# quad_cape.net
KiCad netlist of a schematic drawn in EAGLE
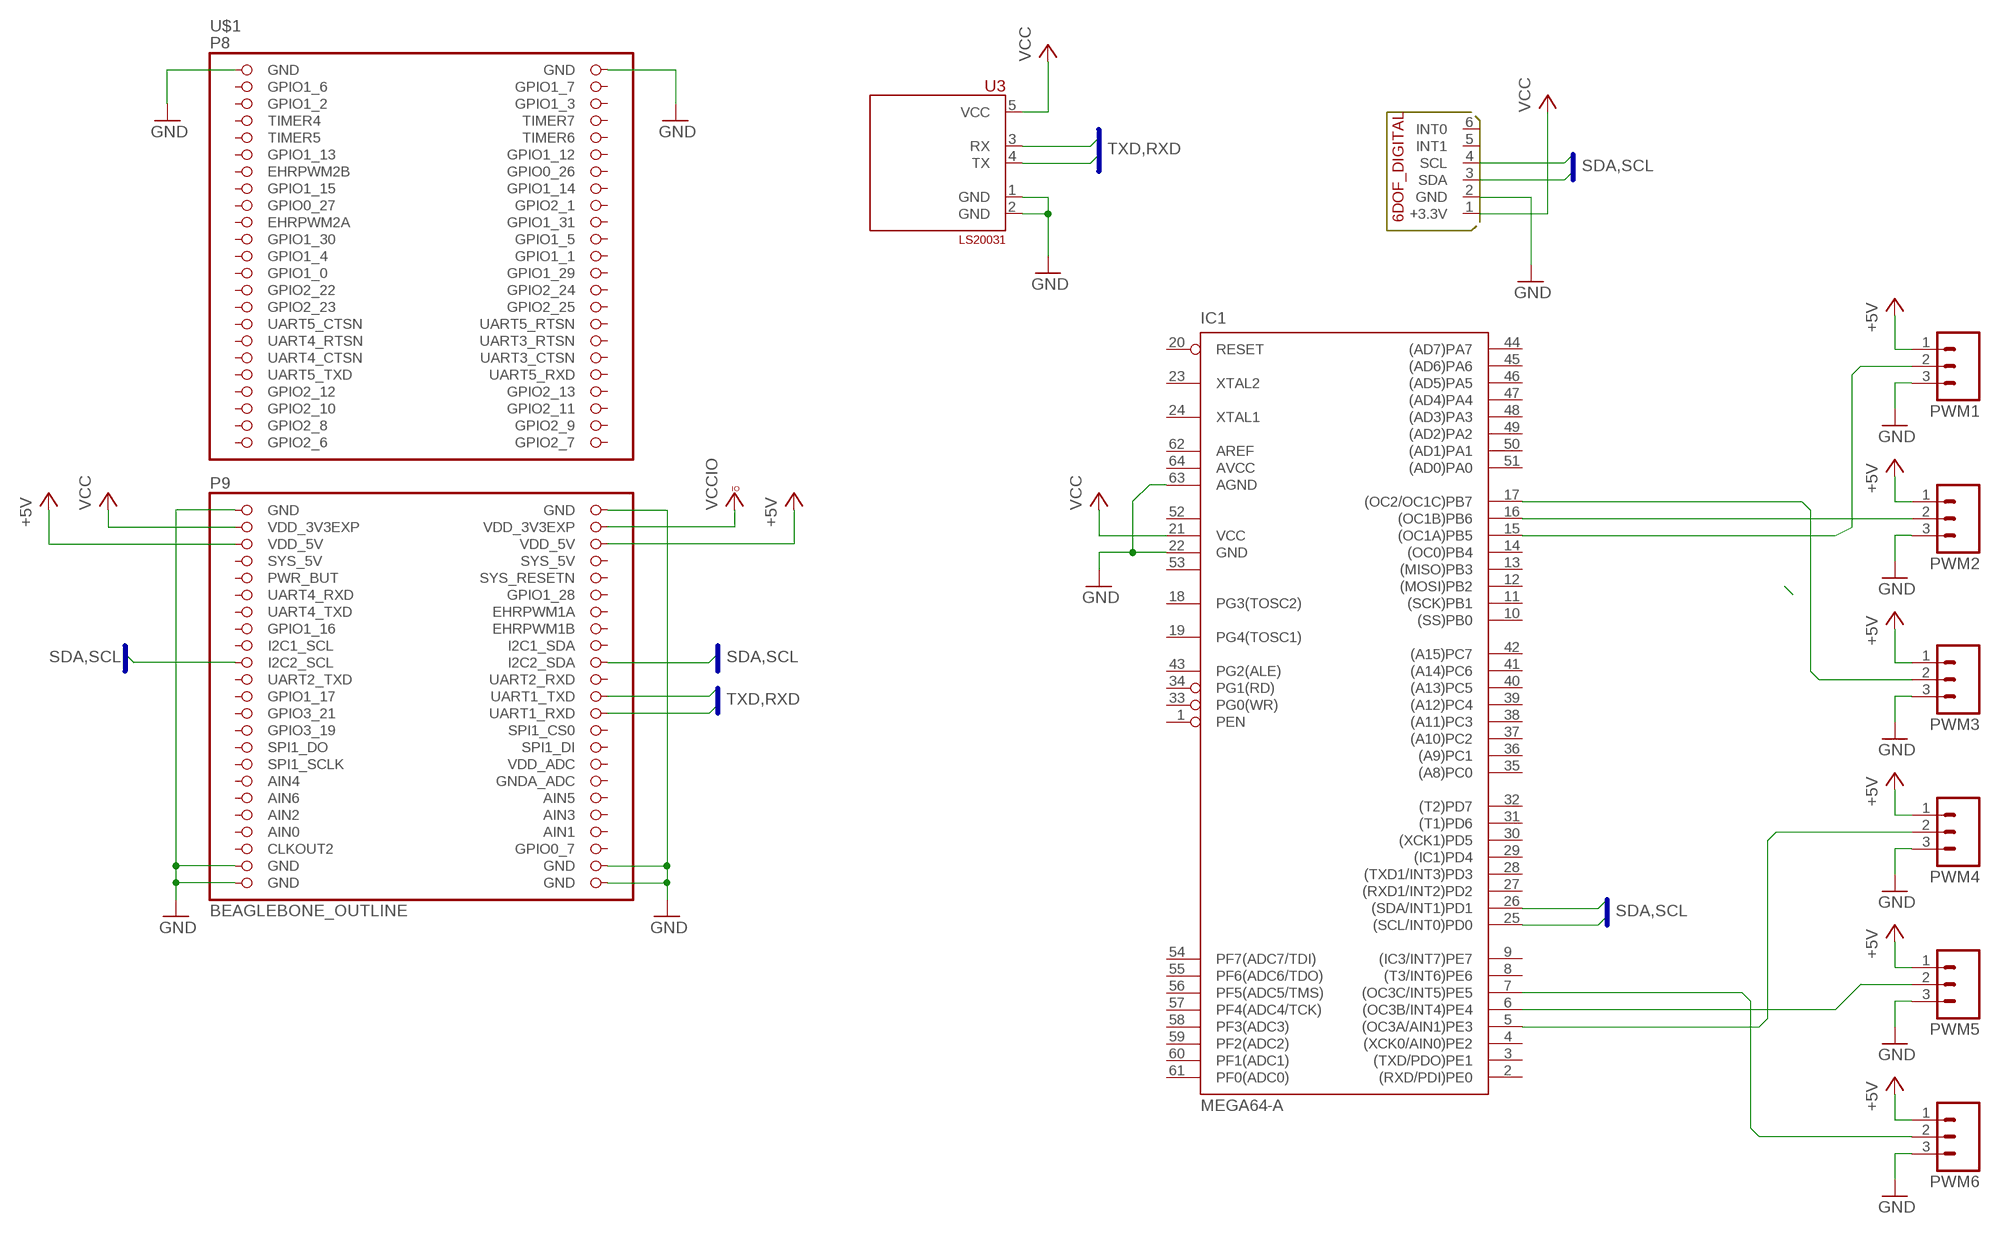
[diagram p0: schematic, sheet 1]

(export (version "E")
  (design (tool "Eeschema 10.0.6"))
  (components
    (comp (ref "IC1")
      (value "MEGA64-A")
      (footprint "eagle-import:TQFP64")
      (libsource (lib "eagle-import") (part "MEGA64-A"))
    )
    (comp (ref "PWM1")
      (value "M03")
      (footprint "eagle-import:JST-3-SMD")
      (libsource (lib "eagle-import") (part "M03"))
    )
    (comp (ref "PWM2")
      (value "M03")
      (footprint "eagle-import:JST-3-SMD")
      (libsource (lib "eagle-import") (part "M03"))
    )
    (comp (ref "PWM3")
      (value "M03")
      (footprint "eagle-import:JST-3-SMD")
      (libsource (lib "eagle-import") (part "M03"))
    )
    (comp (ref "PWM4")
      (value "M03")
      (footprint "eagle-import:JST-3-SMD")
      (libsource (lib "eagle-import") (part "M03"))
    )
    (comp (ref "PWM5")
      (value "M03")
      (footprint "eagle-import:JST-3-SMD")
      (libsource (lib "eagle-import") (part "M03"))
    )
    (comp (ref "PWM6")
      (value "M03")
      (footprint "eagle-import:JST-3-SMD")
      (libsource (lib "eagle-import") (part "M03"))
    )
    (comp (ref "U$1")
      (value "BEAGLEBONE_OUTLINE")
      (footprint "eagle-import:BEAGLEBONE_SHIELD")
      (libsource (lib "eagle-import") (part "BEAGLEBONE_OUTLINE"))
    )
    (comp (ref "U$2")
      (value "6DOF-DIGITAL")
      (footprint "eagle-import:6DOF_DIGITAL_V10")
      (libsource (lib "eagle-import") (part "6DOF-DIGITAL"))
    )
    (comp (ref "U3")
      (value "LS20031")
      (footprint "eagle-import:LS20031")
      (libsource (lib "eagle-import") (part "LS20031"))
    )
  )
  (nets
    (net (code "1") (name "+5V") (class "Default")
      (node (ref "PWM1") (pin "1") (pinfunction "1_1") (pintype "passive"))
      (node (ref "PWM2") (pin "1") (pinfunction "1_1") (pintype "passive"))
      (node (ref "PWM3") (pin "1") (pinfunction "1_1") (pintype "passive"))
      (node (ref "PWM4") (pin "1") (pinfunction "1_1") (pintype "passive"))
      (node (ref "PWM5") (pin "1") (pinfunction "1_1") (pintype "passive"))
      (node (ref "PWM6") (pin "1") (pinfunction "1_1") (pintype "passive"))
      (node (ref "U$1") (pin "51") (pinfunction "VDD_5V_51") (pintype "power_in"))
      (node (ref "U$1") (pin "52") (pinfunction "VDD_5V_52") (pintype "power_in"))
    )
    (net (code "2") (name "/AIN0") (class "Default")
      (node (ref "U$1") (pin "85") (pinfunction "AIN0_85") (pintype "power_in"))
    )
    (net (code "3") (name "/AIN3") (class "Default")
      (node (ref "U$1") (pin "84") (pinfunction "AIN3_84") (pintype "power_in"))
    )
    (net (code "4") (name "/GND1") (class "Default")
      (node (ref "IC1") (pin "53") (pinfunction "GND1_53") (pintype "power_in"))
    )
    (net (code "5") (name "/GPIO1_6") (class "Default")
      (node (ref "U$1") (pin "3") (pinfunction "GPIO1_6_3") (pintype "power_in"))
    )
    (net (code "6") (name "/GPIO1_7") (class "Default")
      (node (ref "U$1") (pin "4") (pinfunction "GPIO1_7_4") (pintype "power_in"))
    )
    (net (code "7") (name "/GPIO2_6") (class "Default")
      (node (ref "U$1") (pin "45") (pinfunction "GPIO2_6_45") (pintype "power_in"))
    )
    (net (code "8") (name "/GPIO2_7") (class "Default")
      (node (ref "U$1") (pin "46") (pinfunction "GPIO2_7_46") (pintype "power_in"))
    )
    (net (code "9") (name "/GPIO2_8") (class "Default")
      (node (ref "U$1") (pin "43") (pinfunction "GPIO2_8_43") (pintype "power_in"))
    )
    (net (code "10") (name "/GPIO2_9") (class "Default")
      (node (ref "U$1") (pin "44") (pinfunction "GPIO2_9_44") (pintype "power_in"))
    )
    (net (code "11") (name "/GPIO2_11") (class "Default")
      (node (ref "U$1") (pin "42") (pinfunction "GPIO2_11_42") (pintype "power_in"))
    )
    (net (code "12") (name "/RXD") (class "Default")
      (node (ref "U$1") (pin "72") (pinfunction "UART1_RXD_72") (pintype "passive"))
      (node (ref "U3") (pin "4") (pinfunction "TX_4") (pintype "output"))
    )
    (net (code "13") (name "/SCL") (class "Default")
      (node (ref "IC1") (pin "25") (pinfunction "(SCL/INT0)PD0_25") (pintype "bidirectional"))
      (node (ref "U$1") (pin "65") (pinfunction "I2C2_SCL_65") (pintype "passive"))
      (node (ref "U$2") (pin "4") (pinfunction "SCL_4") (pintype "bidirectional"))
    )
    (net (code "14") (name "/SDA") (class "Default")
      (node (ref "IC1") (pin "26") (pinfunction "(SDA/INT1)PD1_26") (pintype "bidirectional"))
      (node (ref "U$1") (pin "66") (pinfunction "I2C2_SDA_66") (pintype "passive"))
      (node (ref "U$2") (pin "3") (pinfunction "SDA_3") (pintype "bidirectional"))
    )
    (net (code "15") (name "/TXD") (class "Default")
      (node (ref "U$1") (pin "70") (pinfunction "UART1_TXD_70") (pintype "passive"))
      (node (ref "U3") (pin "3") (pinfunction "RX_3") (pintype "input"))
    )
    (net (code "16") (name "/VCC1") (class "Default")
      (node (ref "IC1") (pin "52") (pinfunction "VCC1_52") (pintype "power_in"))
    )
    (net (code "19") (name "GND") (class "Default")
      (node (ref "IC1") (pin "22") (pinfunction "GND_22") (pintype "power_in"))
      (node (ref "IC1") (pin "63") (pinfunction "AGND_63") (pintype "bidirectional"))
      (node (ref "PWM1") (pin "3") (pinfunction "3_3") (pintype "passive"))
      (node (ref "PWM2") (pin "3") (pinfunction "3_3") (pintype "passive"))
      (node (ref "PWM3") (pin "3") (pinfunction "3_3") (pintype "passive"))
      (node (ref "PWM4") (pin "3") (pinfunction "3_3") (pintype "passive"))
      (node (ref "PWM5") (pin "3") (pinfunction "3_3") (pintype "passive"))
      (node (ref "PWM6") (pin "3") (pinfunction "3_3") (pintype "passive"))
      (node (ref "U$1") (pin "1") (pinfunction "GND_1") (pintype "power_in"))
      (node (ref "U$1") (pin "2") (pinfunction "GND_2") (pintype "power_in"))
      (node (ref "U$1") (pin "47") (pinfunction "GND_47") (pintype "power_in"))
      (node (ref "U$1") (pin "48") (pinfunction "GND_48") (pintype "power_in"))
      (node (ref "U$1") (pin "89") (pinfunction "GND_89") (pintype "input"))
      (node (ref "U$1") (pin "90") (pinfunction "GND_90") (pintype "input"))
      (node (ref "U$1") (pin "91") (pinfunction "GND_91") (pintype "input"))
      (node (ref "U$1") (pin "92") (pinfunction "GND_92") (pintype "input"))
      (node (ref "U$2") (pin "2") (pinfunction "GND_2") (pintype "bidirectional"))
      (node (ref "U3") (pin "1") (pinfunction "GND_1") (pintype "power_in"))
      (node (ref "U3") (pin "2") (pinfunction "GND_2") (pintype "power_in"))
    )
    (net (code "20") (name "Net-(IC1-(OC1A)PB5)") (class "Default")
      (node (ref "IC1") (pin "15") (pinfunction "(OC1A)PB5_15") (pintype "bidirectional"))
      (node (ref "PWM1") (pin "2") (pinfunction "2_2") (pintype "passive"))
    )
    (net (code "21") (name "Net-(IC1-(OC1B)PB6)") (class "Default")
      (node (ref "IC1") (pin "16") (pinfunction "(OC1B)PB6_16") (pintype "bidirectional"))
      (node (ref "PWM2") (pin "2") (pinfunction "2_2") (pintype "passive"))
    )
    (net (code "22") (name "Net-(IC1-(OC2{slash}OC1C)PB7)") (class "Default")
      (node (ref "IC1") (pin "17") (pinfunction "(OC2/OC1C)PB7_17") (pintype "bidirectional"))
      (node (ref "PWM3") (pin "2") (pinfunction "2_2") (pintype "passive"))
    )
    (net (code "23") (name "Net-(IC1-(OC3A{slash}AIN1)PE3)") (class "Default")
      (node (ref "IC1") (pin "5") (pinfunction "(OC3A/AIN1)PE3_5") (pintype "bidirectional"))
      (node (ref "PWM4") (pin "2") (pinfunction "2_2") (pintype "passive"))
    )
    (net (code "24") (name "Net-(IC1-(OC3B{slash}INT4)PE4)") (class "Default")
      (node (ref "IC1") (pin "6") (pinfunction "(OC3B/INT4)PE4_6") (pintype "bidirectional"))
      (node (ref "PWM5") (pin "2") (pinfunction "2_2") (pintype "passive"))
    )
    (net (code "25") (name "Net-(IC1-(OC3C{slash}INT5)PE5)") (class "Default")
      (node (ref "IC1") (pin "7") (pinfunction "(OC3C/INT5)PE5_7") (pintype "bidirectional"))
      (node (ref "PWM6") (pin "2") (pinfunction "2_2") (pintype "passive"))
    )
    (net (code "26") (name "VCC") (class "Default")
      (node (ref "IC1") (pin "21") (pinfunction "VCC_21") (pintype "power_in"))
      (node (ref "U$1") (pin "49") (pinfunction "VDD_3V3EXP_49") (pintype "power_in"))
      (node (ref "U$2") (pin "1") (pinfunction "+3.3V_1") (pintype "bidirectional"))
      (node (ref "U3") (pin "5") (pinfunction "VCC_5") (pintype "power_in"))
    )
    (net (code "27") (name "VCCIO") (class "Default")
      (node (ref "U$1") (pin "50") (pinfunction "VDD_3V3EXP_50") (pintype "power_in"))
    )
    (net (code "28") (name "unconnected-(IC1-(A8)PC0-Pad35)") (class "Default")
      (node (ref "IC1") (pin "35") (pinfunction "(A8)PC0_35") (pintype "output"))
    )
    (net (code "29") (name "unconnected-(IC1-(A9)PC1-Pad36)") (class "Default")
      (node (ref "IC1") (pin "36") (pinfunction "(A9)PC1_36") (pintype "output"))
    )
    (net (code "30") (name "unconnected-(IC1-(A10)PC2-Pad37)") (class "Default")
      (node (ref "IC1") (pin "37") (pinfunction "(A10)PC2_37") (pintype "output"))
    )
    (net (code "31") (name "unconnected-(IC1-(A11)PC3-Pad38)") (class "Default")
      (node (ref "IC1") (pin "38") (pinfunction "(A11)PC3_38") (pintype "output"))
    )
    (net (code "32") (name "unconnected-(IC1-(A12)PC4-Pad39)") (class "Default")
      (node (ref "IC1") (pin "39") (pinfunction "(A12)PC4_39") (pintype "output"))
    )
    (net (code "33") (name "unconnected-(IC1-(A13)PC5-Pad40)") (class "Default")
      (node (ref "IC1") (pin "40") (pinfunction "(A13)PC5_40") (pintype "output"))
    )
    (net (code "34") (name "unconnected-(IC1-(A14)PC6-Pad41)") (class "Default")
      (node (ref "IC1") (pin "41") (pinfunction "(A14)PC6_41") (pintype "output"))
    )
    (net (code "35") (name "unconnected-(IC1-(A15)PC7-Pad42)") (class "Default")
      (node (ref "IC1") (pin "42") (pinfunction "(A15)PC7_42") (pintype "output"))
    )
    (net (code "36") (name "unconnected-(IC1-(AD0)PA0-Pad51)") (class "Default")
      (node (ref "IC1") (pin "51") (pinfunction "(AD0)PA0_51") (pintype "bidirectional"))
    )
    (net (code "37") (name "unconnected-(IC1-(AD1)PA1-Pad50)") (class "Default")
      (node (ref "IC1") (pin "50") (pinfunction "(AD1)PA1_50") (pintype "bidirectional"))
    )
    (net (code "38") (name "unconnected-(IC1-(AD2)PA2-Pad49)") (class "Default")
      (node (ref "IC1") (pin "49") (pinfunction "(AD2)PA2_49") (pintype "bidirectional"))
    )
    (net (code "39") (name "unconnected-(IC1-(AD3)PA3-Pad48)") (class "Default")
      (node (ref "IC1") (pin "48") (pinfunction "(AD3)PA3_48") (pintype "bidirectional"))
    )
    (net (code "40") (name "unconnected-(IC1-(AD4)PA4-Pad47)") (class "Default")
      (node (ref "IC1") (pin "47") (pinfunction "(AD4)PA4_47") (pintype "bidirectional"))
    )
    (net (code "41") (name "unconnected-(IC1-(AD5)PA5-Pad46)") (class "Default")
      (node (ref "IC1") (pin "46") (pinfunction "(AD5)PA5_46") (pintype "bidirectional"))
    )
    (net (code "42") (name "unconnected-(IC1-(AD6)PA6-Pad45)") (class "Default")
      (node (ref "IC1") (pin "45") (pinfunction "(AD6)PA6_45") (pintype "bidirectional"))
    )
    (net (code "43") (name "unconnected-(IC1-(AD7)PA7-Pad44)") (class "Default")
      (node (ref "IC1") (pin "44") (pinfunction "(AD7)PA7_44") (pintype "bidirectional"))
    )
    (net (code "44") (name "unconnected-(IC1-(IC1)PD4-Pad29)") (class "Default")
      (node (ref "IC1") (pin "29") (pinfunction "(IC1)PD4_29") (pintype "bidirectional"))
    )
    (net (code "45") (name "unconnected-(IC1-(IC3{slash}INT7)PE7-Pad9)") (class "Default")
      (node (ref "IC1") (pin "9") (pinfunction "(IC3/INT7)PE7_9") (pintype "bidirectional"))
    )
    (net (code "46") (name "unconnected-(IC1-(MISO)PB3-Pad13)") (class "Default")
      (node (ref "IC1") (pin "13") (pinfunction "(MISO)PB3_13") (pintype "bidirectional"))
    )
    (net (code "47") (name "unconnected-(IC1-(MOSI)PB2-Pad12)") (class "Default")
      (node (ref "IC1") (pin "12") (pinfunction "(MOSI)PB2_12") (pintype "bidirectional"))
    )
    (net (code "48") (name "unconnected-(IC1-(OC0)PB4-Pad14)") (class "Default")
      (node (ref "IC1") (pin "14") (pinfunction "(OC0)PB4_14") (pintype "bidirectional"))
    )
    (net (code "49") (name "unconnected-(IC1-(RXD1{slash}INT2)PD2-Pad27)") (class "Default")
      (node (ref "IC1") (pin "27") (pinfunction "(RXD1/INT2)PD2_27") (pintype "bidirectional"))
    )
    (net (code "50") (name "unconnected-(IC1-(RXD{slash}PDI)PE0-Pad2)") (class "Default")
      (node (ref "IC1") (pin "2") (pinfunction "(RXD/PDI)PE0_2") (pintype "bidirectional"))
    )
    (net (code "51") (name "unconnected-(IC1-(SCK)PB1-Pad11)") (class "Default")
      (node (ref "IC1") (pin "11") (pinfunction "(SCK)PB1_11") (pintype "bidirectional"))
    )
    (net (code "52") (name "unconnected-(IC1-(SS)PB0-Pad10)") (class "Default")
      (node (ref "IC1") (pin "10") (pinfunction "(SS)PB0_10") (pintype "bidirectional"))
    )
    (net (code "53") (name "unconnected-(IC1-(T1)PD6-Pad31)") (class "Default")
      (node (ref "IC1") (pin "31") (pinfunction "(T1)PD6_31") (pintype "bidirectional"))
    )
    (net (code "54") (name "unconnected-(IC1-(T2)PD7-Pad32)") (class "Default")
      (node (ref "IC1") (pin "32") (pinfunction "(T2)PD7_32") (pintype "bidirectional"))
    )
    (net (code "55") (name "unconnected-(IC1-(T3{slash}INT6)PE6-Pad8)") (class "Default")
      (node (ref "IC1") (pin "8") (pinfunction "(T3/INT6)PE6_8") (pintype "bidirectional"))
    )
    (net (code "56") (name "unconnected-(IC1-(TXD1{slash}INT3)PD3-Pad28)") (class "Default")
      (node (ref "IC1") (pin "28") (pinfunction "(TXD1/INT3)PD3_28") (pintype "bidirectional"))
    )
    (net (code "57") (name "unconnected-(IC1-(TXD{slash}PDO)PE1-Pad3)") (class "Default")
      (node (ref "IC1") (pin "3") (pinfunction "(TXD/PDO)PE1_3") (pintype "bidirectional"))
    )
    (net (code "58") (name "unconnected-(IC1-(XCK0{slash}AIN0)PE2-Pad4)") (class "Default")
      (node (ref "IC1") (pin "4") (pinfunction "(XCK0/AIN0)PE2_4") (pintype "bidirectional"))
    )
    (net (code "59") (name "unconnected-(IC1-(XCK1)PD5-Pad30)") (class "Default")
      (node (ref "IC1") (pin "30") (pinfunction "(XCK1)PD5_30") (pintype "bidirectional"))
    )
    (net (code "60") (name "unconnected-(IC1-AREF-Pad62)") (class "Default")
      (node (ref "IC1") (pin "62") (pinfunction "AREF_62") (pintype "bidirectional"))
    )
    (net (code "61") (name "unconnected-(IC1-AVCC-Pad64)") (class "Default")
      (node (ref "IC1") (pin "64") (pinfunction "AVCC_64") (pintype "bidirectional"))
    )
    (net (code "62") (name "unconnected-(IC1-PEN-Pad1)") (class "Default")
      (node (ref "IC1") (pin "1") (pinfunction "PEN_1") (pintype "input"))
    )
    (net (code "63") (name "unconnected-(IC1-PF0(ADC0)-Pad61)") (class "Default")
      (node (ref "IC1") (pin "61") (pinfunction "PF0(ADC0)_61") (pintype "input"))
    )
    (net (code "64") (name "unconnected-(IC1-PF1(ADC1)-Pad60)") (class "Default")
      (node (ref "IC1") (pin "60") (pinfunction "PF1(ADC1)_60") (pintype "input"))
    )
    (net (code "65") (name "unconnected-(IC1-PF2(ADC2)-Pad59)") (class "Default")
      (node (ref "IC1") (pin "59") (pinfunction "PF2(ADC2)_59") (pintype "input"))
    )
    (net (code "66") (name "unconnected-(IC1-PF3(ADC3)-Pad58)") (class "Default")
      (node (ref "IC1") (pin "58") (pinfunction "PF3(ADC3)_58") (pintype "input"))
    )
    (net (code "67") (name "unconnected-(IC1-PF4(ADC4{slash}TCK)-Pad57)") (class "Default")
      (node (ref "IC1") (pin "57") (pinfunction "PF4(ADC4/TCK)_57") (pintype "input"))
    )
    (net (code "68") (name "unconnected-(IC1-PF5(ADC5{slash}TMS)-Pad56)") (class "Default")
      (node (ref "IC1") (pin "56") (pinfunction "PF5(ADC5/TMS)_56") (pintype "input"))
    )
    (net (code "69") (name "unconnected-(IC1-PF6(ADC6{slash}TDO)-Pad55)") (class "Default")
      (node (ref "IC1") (pin "55") (pinfunction "PF6(ADC6/TDO)_55") (pintype "input"))
    )
    (net (code "70") (name "unconnected-(IC1-PF7(ADC7{slash}TDI)-Pad54)") (class "Default")
      (node (ref "IC1") (pin "54") (pinfunction "PF7(ADC7/TDI)_54") (pintype "input"))
    )
    (net (code "71") (name "unconnected-(IC1-PG0(WR)-Pad33)") (class "Default")
      (node (ref "IC1") (pin "33") (pinfunction "PG0(WR)_33") (pintype "bidirectional"))
    )
    (net (code "72") (name "unconnected-(IC1-PG1(RD)-Pad34)") (class "Default")
      (node (ref "IC1") (pin "34") (pinfunction "PG1(RD)_34") (pintype "bidirectional"))
    )
    (net (code "73") (name "unconnected-(IC1-PG2(ALE)-Pad43)") (class "Default")
      (node (ref "IC1") (pin "43") (pinfunction "PG2(ALE)_43") (pintype "bidirectional"))
    )
    (net (code "74") (name "unconnected-(IC1-PG3(TOSC2)-Pad18)") (class "Default")
      (node (ref "IC1") (pin "18") (pinfunction "PG3(TOSC2)_18") (pintype "bidirectional"))
    )
    (net (code "75") (name "unconnected-(IC1-PG4(TOSC1)-Pad19)") (class "Default")
      (node (ref "IC1") (pin "19") (pinfunction "PG4(TOSC1)_19") (pintype "bidirectional"))
    )
    (net (code "76") (name "unconnected-(IC1-RESET-Pad20)") (class "Default")
      (node (ref "IC1") (pin "20") (pinfunction "RESET_20") (pintype "input"))
    )
    (net (code "77") (name "unconnected-(IC1-XTAL1-Pad24)") (class "Default")
      (node (ref "IC1") (pin "24") (pinfunction "XTAL1_24") (pintype "bidirectional"))
    )
    (net (code "78") (name "unconnected-(IC1-XTAL2-Pad23)") (class "Default")
      (node (ref "IC1") (pin "23") (pinfunction "XTAL2_23") (pintype "bidirectional"))
    )
    (net (code "79") (name "unconnected-(U$1-AIN1-Pad86)") (class "Default")
      (node (ref "U$1") (pin "86") (pinfunction "AIN1_86") (pintype "input"))
    )
    (net (code "80") (name "unconnected-(U$1-AIN2-Pad83)") (class "Default")
      (node (ref "U$1") (pin "83") (pinfunction "AIN2_83") (pintype "passive"))
    )
    (net (code "81") (name "unconnected-(U$1-AIN4-Pad79)") (class "Default")
      (node (ref "U$1") (pin "79") (pinfunction "AIN4_79") (pintype "passive"))
    )
    (net (code "82") (name "unconnected-(U$1-AIN5-Pad82)") (class "Default")
      (node (ref "U$1") (pin "82") (pinfunction "AIN5_82") (pintype "passive"))
    )
    (net (code "83") (name "unconnected-(U$1-AIN6-Pad81)") (class "Default")
      (node (ref "U$1") (pin "81") (pinfunction "AIN6_81") (pintype "passive"))
    )
    (net (code "84") (name "unconnected-(U$1-CLKOUT2-Pad87)") (class "Default")
      (node (ref "U$1") (pin "87") (pinfunction "CLKOUT2_87") (pintype "input"))
    )
    (net (code "85") (name "unconnected-(U$1-EHRPWM1A-Pad60)") (class "Default")
      (node (ref "U$1") (pin "60") (pinfunction "EHRPWM1A_60") (pintype "passive"))
    )
    (net (code "86") (name "unconnected-(U$1-EHRPWM1B-Pad62)") (class "Default")
      (node (ref "U$1") (pin "62") (pinfunction "EHRPWM1B_62") (pintype "passive"))
    )
    (net (code "87") (name "unconnected-(U$1-EHRPWM2A-Pad19)") (class "Default")
      (node (ref "U$1") (pin "19") (pinfunction "EHRPWM2A_19") (pintype "passive"))
    )
    (net (code "88") (name "unconnected-(U$1-EHRPWM2B-Pad13)") (class "Default")
      (node (ref "U$1") (pin "13") (pinfunction "EHRPWM2B_13") (pintype "passive"))
    )
    (net (code "89") (name "unconnected-(U$1-GNDA_ADC-Pad80)") (class "Default")
      (node (ref "U$1") (pin "80") (pinfunction "GNDA_ADC_80") (pintype "passive"))
    )
    (net (code "90") (name "unconnected-(U$1-GPIO0_7-Pad88)") (class "Default")
      (node (ref "U$1") (pin "88") (pinfunction "GPIO0_7_88") (pintype "input"))
    )
    (net (code "91") (name "unconnected-(U$1-GPIO0_26-Pad14)") (class "Default")
      (node (ref "U$1") (pin "14") (pinfunction "GPIO0_26_14") (pintype "passive"))
    )
    (net (code "92") (name "unconnected-(U$1-GPIO0_27-Pad17)") (class "Default")
      (node (ref "U$1") (pin "17") (pinfunction "GPIO0_27_17") (pintype "passive"))
    )
    (net (code "93") (name "unconnected-(U$1-GPIO1_0-Pad25)") (class "Default")
      (node (ref "U$1") (pin "25") (pinfunction "GPIO1_0_25") (pintype "passive"))
    )
    (net (code "94") (name "unconnected-(U$1-GPIO1_1-Pad24)") (class "Default")
      (node (ref "U$1") (pin "24") (pinfunction "GPIO1_1_24") (pintype "passive"))
    )
    (net (code "95") (name "unconnected-(U$1-GPIO1_2-Pad5)") (class "Default")
      (node (ref "U$1") (pin "5") (pinfunction "GPIO1_2_5") (pintype "passive"))
    )
    (net (code "96") (name "unconnected-(U$1-GPIO1_3-Pad6)") (class "Default")
      (node (ref "U$1") (pin "6") (pinfunction "GPIO1_3_6") (pintype "passive"))
    )
    (net (code "97") (name "unconnected-(U$1-GPIO1_4-Pad23)") (class "Default")
      (node (ref "U$1") (pin "23") (pinfunction "GPIO1_4_23") (pintype "passive"))
    )
    (net (code "98") (name "unconnected-(U$1-GPIO1_5-Pad22)") (class "Default")
      (node (ref "U$1") (pin "22") (pinfunction "GPIO1_5_22") (pintype "passive"))
    )
    (net (code "99") (name "unconnected-(U$1-GPIO1_12-Pad12)") (class "Default")
      (node (ref "U$1") (pin "12") (pinfunction "GPIO1_12_12") (pintype "passive"))
    )
    (net (code "100") (name "unconnected-(U$1-GPIO1_13-Pad11)") (class "Default")
      (node (ref "U$1") (pin "11") (pinfunction "GPIO1_13_11") (pintype "passive"))
    )
    (net (code "101") (name "unconnected-(U$1-GPIO1_14-Pad16)") (class "Default")
      (node (ref "U$1") (pin "16") (pinfunction "GPIO1_14_16") (pintype "passive"))
    )
    (net (code "102") (name "unconnected-(U$1-GPIO1_15-Pad15)") (class "Default")
      (node (ref "U$1") (pin "15") (pinfunction "GPIO1_15_15") (pintype "passive"))
    )
    (net (code "103") (name "unconnected-(U$1-GPIO1_16-Pad61)") (class "Default")
      (node (ref "U$1") (pin "61") (pinfunction "GPIO1_16_61") (pintype "passive"))
    )
    (net (code "104") (name "unconnected-(U$1-GPIO1_17-Pad69)") (class "Default")
      (node (ref "U$1") (pin "69") (pinfunction "GPIO1_17_69") (pintype "passive"))
    )
    (net (code "105") (name "unconnected-(U$1-GPIO1_28-Pad58)") (class "Default")
      (node (ref "U$1") (pin "58") (pinfunction "GPIO1_28_58") (pintype "passive"))
    )
    (net (code "106") (name "unconnected-(U$1-GPIO1_29-Pad26)") (class "Default")
      (node (ref "U$1") (pin "26") (pinfunction "GPIO1_29_26") (pintype "passive"))
    )
    (net (code "107") (name "unconnected-(U$1-GPIO1_30-Pad21)") (class "Default")
      (node (ref "U$1") (pin "21") (pinfunction "GPIO1_30_21") (pintype "passive"))
    )
    (net (code "108") (name "unconnected-(U$1-GPIO1_31-Pad20)") (class "Default")
      (node (ref "U$1") (pin "20") (pinfunction "GPIO1_31_20") (pintype "passive"))
    )
    (net (code "109") (name "unconnected-(U$1-GPIO2_1-Pad18)") (class "Default")
      (node (ref "U$1") (pin "18") (pinfunction "GPIO2_1_18") (pintype "passive"))
    )
    (net (code "110") (name "unconnected-(U$1-GPIO2_10-Pad41)") (class "Default")
      (node (ref "U$1") (pin "41") (pinfunction "GPIO2_10_41") (pintype "passive"))
    )
    (net (code "111") (name "unconnected-(U$1-GPIO2_12-Pad39)") (class "Default")
      (node (ref "U$1") (pin "39") (pinfunction "GPIO2_12_39") (pintype "passive"))
    )
    (net (code "112") (name "unconnected-(U$1-GPIO2_13-Pad40)") (class "Default")
      (node (ref "U$1") (pin "40") (pinfunction "GPIO2_13_40") (pintype "passive"))
    )
    (net (code "113") (name "unconnected-(U$1-GPIO2_22-Pad27)") (class "Default")
      (node (ref "U$1") (pin "27") (pinfunction "GPIO2_22_27") (pintype "passive"))
    )
    (net (code "114") (name "unconnected-(U$1-GPIO2_23-Pad29)") (class "Default")
      (node (ref "U$1") (pin "29") (pinfunction "GPIO2_23_29") (pintype "passive"))
    )
    (net (code "115") (name "unconnected-(U$1-GPIO2_24-Pad28)") (class "Default")
      (node (ref "U$1") (pin "28") (pinfunction "GPIO2_24_28") (pintype "passive"))
    )
    (net (code "116") (name "unconnected-(U$1-GPIO2_25-Pad30)") (class "Default")
      (node (ref "U$1") (pin "30") (pinfunction "GPIO2_25_30") (pintype "passive"))
    )
    (net (code "117") (name "unconnected-(U$1-GPIO3_19-Pad73)") (class "Default")
      (node (ref "U$1") (pin "73") (pinfunction "GPIO3_19_73") (pintype "passive"))
    )
    (net (code "118") (name "unconnected-(U$1-GPIO3_21-Pad71)") (class "Default")
      (node (ref "U$1") (pin "71") (pinfunction "GPIO3_21_71") (pintype "passive"))
    )
    (net (code "119") (name "unconnected-(U$1-I2C1_SCL-Pad63)") (class "Default")
      (node (ref "U$1") (pin "63") (pinfunction "I2C1_SCL_63") (pintype "passive"))
    )
    (net (code "120") (name "unconnected-(U$1-I2C1_SDA-Pad64)") (class "Default")
      (node (ref "U$1") (pin "64") (pinfunction "I2C1_SDA_64") (pintype "passive"))
    )
    (net (code "121") (name "unconnected-(U$1-PWR_BUT-Pad55)") (class "Default")
      (node (ref "U$1") (pin "55") (pinfunction "PWR_BUT_55") (pintype "passive"))
    )
    (net (code "122") (name "unconnected-(U$1-SPI1_CS0-Pad74)") (class "Default")
      (node (ref "U$1") (pin "74") (pinfunction "SPI1_CS0_74") (pintype "passive"))
    )
    (net (code "123") (name "unconnected-(U$1-SPI1_DI-Pad76)") (class "Default")
      (node (ref "U$1") (pin "76") (pinfunction "SPI1_DI_76") (pintype "passive"))
    )
    (net (code "124") (name "unconnected-(U$1-SPI1_DO-Pad75)") (class "Default")
      (node (ref "U$1") (pin "75") (pinfunction "SPI1_DO_75") (pintype "passive"))
    )
    (net (code "125") (name "unconnected-(U$1-SPI1_SCLK-Pad77)") (class "Default")
      (node (ref "U$1") (pin "77") (pinfunction "SPI1_SCLK_77") (pintype "passive"))
    )
    (net (code "126") (name "unconnected-(U$1-SYS_5V-Pad53)") (class "Default")
      (node (ref "U$1") (pin "53") (pinfunction "SYS_5V_53") (pintype "passive"))
    )
    (net (code "127") (name "unconnected-(U$1-SYS_5V-Pad54)") (class "Default")
      (node (ref "U$1") (pin "54") (pinfunction "SYS_5V_54") (pintype "passive"))
    )
    (net (code "128") (name "unconnected-(U$1-SYS_RESETN-Pad56)") (class "Default")
      (node (ref "U$1") (pin "56") (pinfunction "SYS_RESETN_56") (pintype "passive"))
    )
    (net (code "129") (name "unconnected-(U$1-TIMER4-Pad7)") (class "Default")
      (node (ref "U$1") (pin "7") (pinfunction "TIMER4_7") (pintype "passive"))
    )
    (net (code "130") (name "unconnected-(U$1-TIMER5-Pad9)") (class "Default")
      (node (ref "U$1") (pin "9") (pinfunction "TIMER5_9") (pintype "passive"))
    )
    (net (code "131") (name "unconnected-(U$1-TIMER6-Pad10)") (class "Default")
      (node (ref "U$1") (pin "10") (pinfunction "TIMER6_10") (pintype "passive"))
    )
    (net (code "132") (name "unconnected-(U$1-TIMER7-Pad8)") (class "Default")
      (node (ref "U$1") (pin "8") (pinfunction "TIMER7_8") (pintype "passive"))
    )
    (net (code "133") (name "unconnected-(U$1-UART2_RXD-Pad68)") (class "Default")
      (node (ref "U$1") (pin "68") (pinfunction "UART2_RXD_68") (pintype "passive"))
    )
    (net (code "134") (name "unconnected-(U$1-UART2_TXD-Pad67)") (class "Default")
      (node (ref "U$1") (pin "67") (pinfunction "UART2_TXD_67") (pintype "passive"))
    )
    (net (code "135") (name "unconnected-(U$1-UART3_CTSN-Pad36)") (class "Default")
      (node (ref "U$1") (pin "36") (pinfunction "UART3_CTSN_36") (pintype "passive"))
    )
    (net (code "136") (name "unconnected-(U$1-UART3_RTSN-Pad34)") (class "Default")
      (node (ref "U$1") (pin "34") (pinfunction "UART3_RTSN_34") (pintype "passive"))
    )
    (net (code "137") (name "unconnected-(U$1-UART4_CTSN-Pad35)") (class "Default")
      (node (ref "U$1") (pin "35") (pinfunction "UART4_CTSN_35") (pintype "passive"))
    )
    (net (code "138") (name "unconnected-(U$1-UART4_RTSN-Pad33)") (class "Default")
      (node (ref "U$1") (pin "33") (pinfunction "UART4_RTSN_33") (pintype "passive"))
    )
    (net (code "139") (name "unconnected-(U$1-UART4_RXD-Pad57)") (class "Default")
      (node (ref "U$1") (pin "57") (pinfunction "UART4_RXD_57") (pintype "passive"))
    )
    (net (code "140") (name "unconnected-(U$1-UART4_TXD-Pad59)") (class "Default")
      (node (ref "U$1") (pin "59") (pinfunction "UART4_TXD_59") (pintype "passive"))
    )
    (net (code "141") (name "unconnected-(U$1-UART5_CTSN-Pad31)") (class "Default")
      (node (ref "U$1") (pin "31") (pinfunction "UART5_CTSN_31") (pintype "passive"))
    )
    (net (code "142") (name "unconnected-(U$1-UART5_RTSN-Pad32)") (class "Default")
      (node (ref "U$1") (pin "32") (pinfunction "UART5_RTSN_32") (pintype "passive"))
    )
    (net (code "143") (name "unconnected-(U$1-UART5_RXD-Pad38)") (class "Default")
      (node (ref "U$1") (pin "38") (pinfunction "UART5_RXD_38") (pintype "passive"))
    )
    (net (code "144") (name "unconnected-(U$1-UART5_TXD-Pad37)") (class "Default")
      (node (ref "U$1") (pin "37") (pinfunction "UART5_TXD_37") (pintype "passive"))
    )
    (net (code "145") (name "unconnected-(U$1-VDD_ADC-Pad78)") (class "Default")
      (node (ref "U$1") (pin "78") (pinfunction "VDD_ADC_78") (pintype "passive"))
    )
    (net (code "146") (name "unconnected-(U$2-INT0-Pad6)") (class "Default")
      (node (ref "U$2") (pin "6") (pinfunction "INT0_6") (pintype "bidirectional"))
    )
    (net (code "147") (name "unconnected-(U$2-INT1-Pad5)") (class "Default")
      (node (ref "U$2") (pin "5") (pinfunction "INT1_5") (pintype "bidirectional"))
    )
  )
)
